# Electronic_Scheme_to_Resert_Circuit_2021.net
KiCad netlist of a schematic drawn in Altium Designer
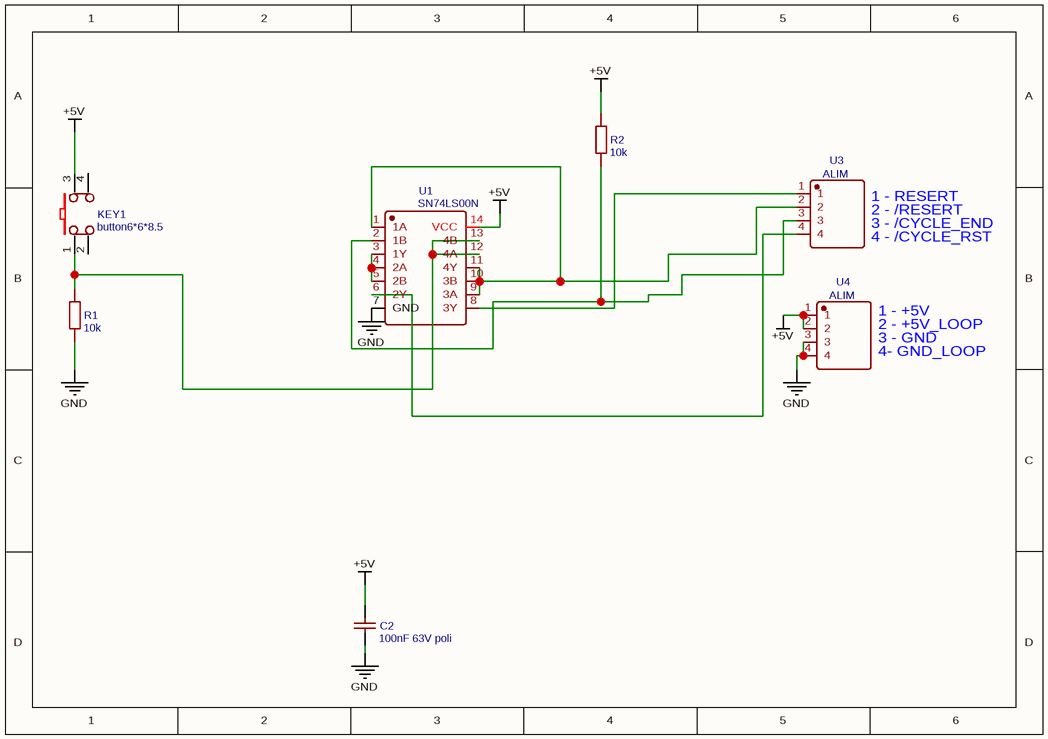
[diagram p0: Electronic Scheme to Resert Circuit_2021-10-20.schdoc]

(export (version "E")
  (design (tool "Eeschema 10.0.6"))
  (components
    (comp (ref "C2")
      (value "100nF 63V poli")
      (fields
        (field (name "BOM_MANUFACTURER PART") "0.01uF(103) 100V")
        (field (name "BOM_SUPPLIER PART") "C10722")
      )
      (libsource (lib "altium-import") (part "root_3_100nF 63V poli_"))
    )
    (comp (ref "KEY1")
      (value "button6*6*8.5")
      (fields (field (name "BOM_SUPPLIER PART") "C59980"))
      (libsource (lib "altium-import") (part "root_1_button6*6*8.5_"))
    )
    (comp (ref "R1")
      (value "10k")
      (fields (field (name "BOM_SUPPLIER PART") "C119997") (field (name "CONTRIBUTOR") "LCSC"))
      (libsource (lib "altium-import") (part "root_3_10k_"))
    )
    (comp (ref "R2")
      (value "10k")
      (fields (field (name "BOM_SUPPLIER PART") "C119997") (field (name "CONTRIBUTOR") "LCSC"))
      (libsource (lib "altium-import") (part "root_3_10k_"))
    )
    (comp (ref "U1")
      (value "SN74LS00N")
      (fields (field (name "BOM_SUPPLIER PART") "C181629") (field (name "CONTRIBUTOR") "LCSC"))
      (libsource (lib "altium-import") (part "root_0_SN74LS00N_"))
    )
    (comp (ref "U3")
      (value "ALIM")
      (fields
        (field (name "BOM_SUPPLIER PART") "C210162")
        (field (name "BOM_MANUFACTURER PART") "171825-4")
        (field (name "CONTRIBUTOR") "LCSC")
      )
      (libsource (lib "altium-import") (part "root_0_ALIM_"))
    )
    (comp (ref "U4")
      (value "ALIM")
      (fields
        (field (name "BOM_SUPPLIER PART") "C210162")
        (field (name "BOM_MANUFACTURER PART") "171825-4")
        (field (name "CONTRIBUTOR") "LCSC")
      )
      (libsource (lib "altium-import") (part "root_0_ALIM_"))
    )
  )
  (nets
    (net (code "1") (name "+5V") (class "Default")
      (node (ref "C2") (pin "1") (pinfunction "1_1") (pintype "passive"))
      (node (ref "KEY1") (pin "3") (pinfunction "3_3") (pintype "passive"))
      (node (ref "R2") (pin "1") (pinfunction "1_1") (pintype "passive"))
      (node (ref "U1") (pin "14") (pinfunction "VCC_14") (pintype "passive"))
      (node (ref "U4") (pin "1") (pinfunction "1_1") (pintype "passive"))
      (node (ref "U4") (pin "2") (pinfunction "2_2") (pintype "passive"))
    )
    (net (code "2") (name "GND") (class "Default")
      (node (ref "C2") (pin "2") (pinfunction "2_2") (pintype "passive"))
      (node (ref "R1") (pin "2") (pinfunction "2_2") (pintype "passive"))
      (node (ref "U1") (pin "7") (pinfunction "GND_7") (pintype "passive"))
      (node (ref "U4") (pin "3") (pinfunction "3_3") (pintype "passive"))
      (node (ref "U4") (pin "4") (pinfunction "4_4") (pintype "passive"))
    )
    (net (code "3") (name "Net-(U1-1A)") (class "Default")
      (node (ref "U1") (pin "1") (pinfunction "1A_1") (pintype "passive"))
      (node (ref "U1") (pin "10") (pinfunction "3B_10") (pintype "passive"))
      (node (ref "U1") (pin "11") (pinfunction "4Y_11") (pintype "passive"))
      (node (ref "U1") (pin "9") (pinfunction "3A_9") (pintype "passive"))
      (node (ref "U3") (pin "2") (pinfunction "2_2") (pintype "passive"))
    )
    (net (code "4") (name "Net-(U1-1B)") (class "Default")
      (node (ref "R2") (pin "2") (pinfunction "2_2") (pintype "passive"))
      (node (ref "U1") (pin "2") (pinfunction "1B_2") (pintype "passive"))
      (node (ref "U3") (pin "3") (pinfunction "3_3") (pintype "passive"))
    )
    (net (code "5") (name "Net-(U1-1Y)") (class "Default")
      (node (ref "U1") (pin "3") (pinfunction "1Y_3") (pintype "passive"))
      (node (ref "U1") (pin "4") (pinfunction "2A_4") (pintype "passive"))
      (node (ref "U1") (pin "5") (pinfunction "2B_5") (pintype "passive"))
    )
    (net (code "6") (name "Net-(U1-2Y)") (class "Default")
      (node (ref "U1") (pin "6") (pinfunction "2Y_6") (pintype "passive"))
      (node (ref "U3") (pin "4") (pinfunction "4_4") (pintype "passive"))
    )
    (net (code "7") (name "Net-(U1-3Y)") (class "Default")
      (node (ref "U1") (pin "8") (pinfunction "3Y_8") (pintype "passive"))
      (node (ref "U3") (pin "1") (pinfunction "1_1") (pintype "passive"))
    )
    (net (code "8") (name "Net-(U1-4A)") (class "Default")
      (node (ref "KEY1") (pin "1") (pinfunction "1_1") (pintype "passive"))
      (node (ref "R1") (pin "1") (pinfunction "1_1") (pintype "passive"))
      (node (ref "U1") (pin "12") (pinfunction "4A_12") (pintype "passive"))
      (node (ref "U1") (pin "13") (pinfunction "4B_13") (pintype "passive"))
    )
    (net (code "9") (name "unconnected-(KEY1-Pad2)") (class "Default")
      (node (ref "KEY1") (pin "2") (pinfunction "2_2") (pintype "passive"))
    )
    (net (code "10") (name "unconnected-(KEY1-Pad4)") (class "Default")
      (node (ref "KEY1") (pin "4") (pinfunction "4_4") (pintype "passive"))
    )
  )
)
